# main.net
KiCad netlist of a schematic drawn in EAGLE
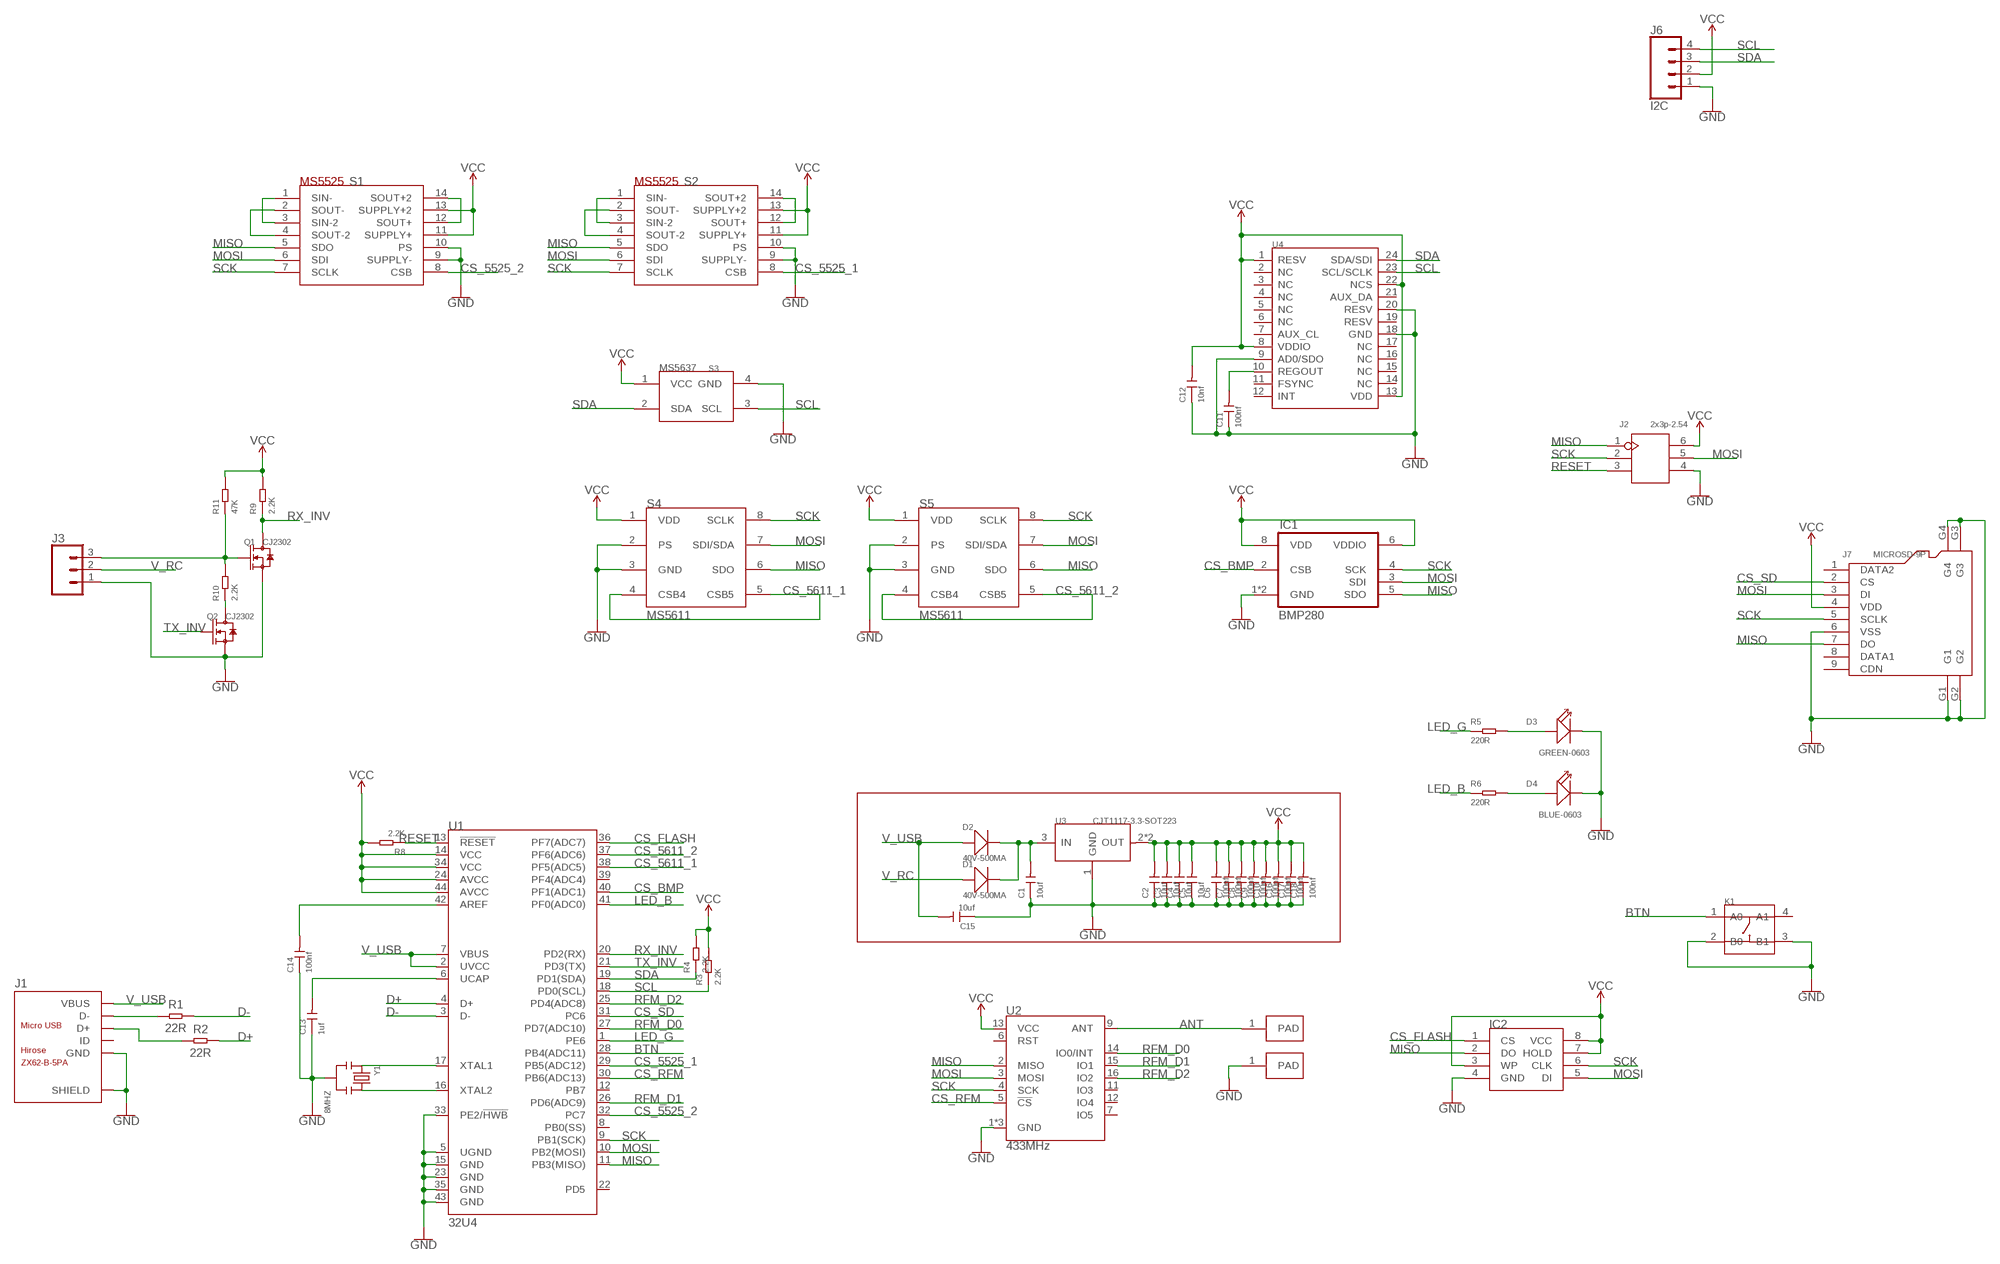
[diagram p0: schematic, sheet 1]

(export (version "E")
  (design (tool "Eeschema 10.0.6"))
  (components
    (comp (ref "C1")
      (value "10uf")
      (footprint "eagle-import:C0805")
      (fields (field (name "MPN") "CC0805KKX5R8BB106"))
      (libsource (lib "eagle-import") (part "CERAMIC-10UF-25V-10%-X5R(0805)"))
    )
    (comp (ref "C2")
      (value "10uf")
      (footprint "eagle-import:C0805")
      (fields (field (name "MPN") "CC0805KKX5R8BB106"))
      (libsource (lib "eagle-import") (part "CERAMIC-10UF-25V-10%-X5R(0805)"))
    )
    (comp (ref "C3")
      (value "10uf")
      (footprint "eagle-import:C0805")
      (fields (field (name "MPN") "CC0805KKX5R8BB106"))
      (libsource (lib "eagle-import") (part "CERAMIC-10UF-25V-10%-X5R(0805)"))
    )
    (comp (ref "C4")
      (value "10uf")
      (footprint "eagle-import:C0805")
      (fields (field (name "MPN") "CC0805KKX5R8BB106"))
      (libsource (lib "eagle-import") (part "CERAMIC-10UF-25V-10%-X5R(0805)"))
    )
    (comp (ref "C5")
      (value "10uf")
      (footprint "eagle-import:C0805")
      (fields (field (name "MPN") "CC0805KKX5R8BB106"))
      (libsource (lib "eagle-import") (part "CERAMIC-10UF-25V-10%-X5R(0805)"))
    )
    (comp (ref "C6")
      (value "100nf")
      (footprint "eagle-import:C0603")
      (fields (field (name "MPN") "CC0603KRX7R9BB104"))
      (libsource (lib "eagle-import") (part "CERAMIC-100NF-50V-10%-X7R(0603)"))
    )
    (comp (ref "C7")
      (value "100nf")
      (footprint "eagle-import:C0603")
      (fields (field (name "MPN") "CC0603KRX7R9BB104"))
      (libsource (lib "eagle-import") (part "CERAMIC-100NF-50V-10%-X7R(0603)"))
    )
    (comp (ref "C8")
      (value "100nf")
      (footprint "eagle-import:C0603")
      (fields (field (name "MPN") "CC0603KRX7R9BB104"))
      (libsource (lib "eagle-import") (part "CERAMIC-100NF-50V-10%-X7R(0603)"))
    )
    (comp (ref "C9")
      (value "100nf")
      (footprint "eagle-import:C0603")
      (fields (field (name "MPN") "CC0603KRX7R9BB104"))
      (libsource (lib "eagle-import") (part "CERAMIC-100NF-50V-10%-X7R(0603)"))
    )
    (comp (ref "C10")
      (value "100nf")
      (footprint "eagle-import:C0603")
      (fields (field (name "MPN") "CC0603KRX7R9BB104"))
      (libsource (lib "eagle-import") (part "CERAMIC-100NF-50V-10%-X7R(0603)"))
    )
    (comp (ref "C11")
      (value "100nf")
      (footprint "eagle-import:C0603")
      (fields (field (name "MPN") "CC0603KRX7R9BB104"))
      (libsource (lib "eagle-import") (part "CERAMIC-100NF-50V-10%-X7R(0603)"))
    )
    (comp (ref "C12")
      (value "10nf")
      (footprint "eagle-import:C0603")
      (fields (field (name "MPN") "CC0603KRX7R9BB103"))
      (libsource (lib "eagle-import") (part "CERAMIC-10NF-50V-10%-X7R(0603)"))
    )
    (comp (ref "C13")
      (value "1uf")
      (footprint "eagle-import:C0603")
      (fields (field (name "MPN") "CC0603KRX7R8BB105"))
      (libsource (lib "eagle-import") (part "CERAMIC-1UF-25V-10%-X7R(0603)"))
    )
    (comp (ref "C14")
      (value "100nf")
      (footprint "eagle-import:C0603")
      (fields (field (name "MPN") "CC0603KRX7R9BB104"))
      (libsource (lib "eagle-import") (part "CERAMIC-100NF-50V-10%-X7R(0603)"))
    )
    (comp (ref "C15")
      (value "10uf")
      (footprint "eagle-import:C0805")
      (fields (field (name "MPN") "CC0805KKX5R8BB106"))
      (libsource (lib "eagle-import") (part "CERAMIC-10UF-25V-10%-X5R(0805)"))
    )
    (comp (ref "C16")
      (value "100nf")
      (footprint "eagle-import:C0603")
      (fields (field (name "MPN") "CC0603KRX7R9BB104"))
      (libsource (lib "eagle-import") (part "CERAMIC-100NF-50V-10%-X7R(0603)"))
    )
    (comp (ref "C17")
      (value "100nf")
      (footprint "eagle-import:C0603")
      (fields (field (name "MPN") "CC0603KRX7R9BB104"))
      (libsource (lib "eagle-import") (part "CERAMIC-100NF-50V-10%-X7R(0603)"))
    )
    (comp (ref "C18")
      (value "100nf")
      (footprint "eagle-import:C0603")
      (fields (field (name "MPN") "CC0603KRX7R9BB104"))
      (libsource (lib "eagle-import") (part "CERAMIC-100NF-50V-10%-X7R(0603)"))
    )
    (comp (ref "D1")
      (value "40V-500MA")
      (footprint "eagle-import:SOD-123")
      (fields (field (name "MPN") "B0540W"))
      (libsource (lib "eagle-import") (part "SMD-DIODE-SCHOTTKY-40V-500MA(SOD-123)"))
    )
    (comp (ref "D2")
      (value "40V-500MA")
      (footprint "eagle-import:SOD-123")
      (fields (field (name "MPN") "B0540W"))
      (libsource (lib "eagle-import") (part "SMD-DIODE-SCHOTTKY-40V-500MA(SOD-123)"))
    )
    (comp (ref "D3")
      (value "GREEN-0603")
      (footprint "eagle-import:LED-0603")
      (fields (field (name "MPN") "19-217-G7C-AN1P2-3T"))
      (libsource (lib "eagle-import") (part "SMD-LED-CLEAR-GREEN(0603)"))
    )
    (comp (ref "D4")
      (value "BLUE-0603")
      (footprint "eagle-import:LED-0603")
      (fields (field (name "MPN") "19-217-BHC-ZL1M2RY-3T"))
      (libsource (lib "eagle-import") (part "SMD-LED-CLEAR-BLUE(0603)"))
    )
    (comp (ref "IC1")
      (value "BMP280")
      (footprint "eagle-import:BMP280")
      (libsource (lib "eagle-import") (part "BMP280"))
    )
    (comp (ref "IC2")
      (value "W25Q32BVWSON8_6X5")
      (footprint "eagle-import:SON127P600X500X75-8")
      (libsource (lib "eagle-import") (part "W25Q32BVWSON8_6X5"))
    )
    (comp (ref "J1")
      (value "ZX62-B-5PA")
      (footprint "eagle-import:MICRO-USB5+6P-SMD-0.65-AB")
      (libsource (lib "eagle-import") (part "MICRO-USB-SMD(ZX62-B-5PA)"))
    )
    (comp (ref "J2")
      (value "2x3p-2.54")
      (footprint "eagle-import:H2X3-2.54")
      (fields (field (name "MPN") "P125-12A1BS116A1"))
      (libsource (lib "eagle-import") (part "DIP-BLACK-MALE-HEADER(2X3P-2.54）-2.54"))
    )
    (comp (ref "J3")
      (value "CONN_03")
      (footprint "eagle-import:1X03")
      (libsource (lib "eagle-import") (part "CONN_03"))
    )
    (comp (ref "J6")
      (value "I2C")
      (footprint "eagle-import:1X04")
      (libsource (lib "eagle-import") (part "CONN_04"))
    )
    (comp (ref "J7")
      (value "MICROSD-9P")
      (footprint "eagle-import:MICRO-SD9+4P-SMD-16.1X14.5X1.85MM")
      (libsource (lib "eagle-import") (part "MICRO-SD-CARD-HOLDER-9P"))
    )
    (comp (ref "K1")
      (value "SMD-SWITCH-TACTILE-SPST-NO(4P-D6.0MM)")
      (footprint "eagle-import:SW4-SMD-6.0X6.0X5.0MM")
      (fields (field (name "MPN") "DTSM-62K-S-V-T/R(SN431)"))
      (libsource (lib "eagle-import") (part "SMD-SWITCH-TACTILE-SPST-NO(4P-D6.0MM)"))
    )
    (comp (ref "Q1")
      (value "CJ2302")
      (footprint "eagle-import:SOT-23")
      (libsource (lib "eagle-import") (part "SMD-MOSFET-N-CH-20V-2.1A-CJ2302(SOT-23)"))
    )
    (comp (ref "Q2")
      (value "CJ2302")
      (footprint "eagle-import:SOT-23")
      (libsource (lib "eagle-import") (part "SMD-MOSFET-N-CH-20V-2.1A-CJ2302(SOT-23)"))
    )
    (comp (ref "R1")
      (value "22R")
      (footprint "eagle-import:R0603")
      (fields (field (name "MPN") "RC0603JR-0722RL"))
      (libsource (lib "eagle-import") (part "SMD-RES-22R-5%-1/10W(0603)"))
    )
    (comp (ref "R2")
      (value "22R")
      (footprint "eagle-import:R0603")
      (fields (field (name "MPN") "RC0603JR-0722RL"))
      (libsource (lib "eagle-import") (part "SMD-RES-22R-5%-1/10W(0603)"))
    )
    (comp (ref "R3")
      (value "2.2K")
      (footprint "eagle-import:R0603")
      (fields (field (name "MPN") "RC0603JR-072K2L"))
      (libsource (lib "eagle-import") (part "SMD-RES-2.2K-5%-1/10W(0603)"))
    )
    (comp (ref "R4")
      (value "2.2K")
      (footprint "eagle-import:R0603")
      (fields (field (name "MPN") "RC0603JR-072K2L"))
      (libsource (lib "eagle-import") (part "SMD-RES-2.2K-5%-1/10W(0603)"))
    )
    (comp (ref "R5")
      (value "220R")
      (footprint "eagle-import:R0603")
      (fields (field (name "MPN") "RC0603JR-07220RL"))
      (libsource (lib "eagle-import") (part "SMD-RES-220R-5%-1/10W(0603)"))
    )
    (comp (ref "R6")
      (value "220R")
      (footprint "eagle-import:R0603")
      (fields (field (name "MPN") "RC0603JR-07220RL"))
      (libsource (lib "eagle-import") (part "SMD-RES-220R-5%-1/10W(0603)"))
    )
    (comp (ref "R8")
      (value "2.2K")
      (footprint "eagle-import:R0603")
      (fields (field (name "MPN") "RC0603JR-072K2L"))
      (libsource (lib "eagle-import") (part "SMD-RES-2.2K-5%-1/10W(0603)"))
    )
    (comp (ref "R9")
      (value "2.2K")
      (footprint "eagle-import:R0603")
      (fields (field (name "MPN") "RC0603JR-072K2L"))
      (libsource (lib "eagle-import") (part "SMD-RES-2.2K-5%-1/10W(0603)"))
    )
    (comp (ref "R10")
      (value "2.2K")
      (footprint "eagle-import:R0603")
      (fields (field (name "MPN") "RC0603JR-072K2L"))
      (libsource (lib "eagle-import") (part "SMD-RES-2.2K-5%-1/10W(0603)"))
    )
    (comp (ref "R11")
      (value "47K")
      (footprint "eagle-import:R0603")
      (fields (field (name "MPN") "RC0603JR-0747KL"))
      (libsource (lib "eagle-import") (part "SMD-RES-47K-5%-1/10W(0603)"))
    )
    (comp (ref "S1")
      (value "MS5525")
      (footprint "eagle-import:SOIC14-WIDE")
      (libsource (lib "eagle-import") (part "MS5525"))
    )
    (comp (ref "S2")
      (value "MS5525")
      (footprint "eagle-import:SOIC14-WIDE")
      (libsource (lib "eagle-import") (part "MS5525"))
    )
    (comp (ref "S3")
      (value "MS5637")
      (footprint "eagle-import:MS5637")
      (libsource (lib "eagle-import") (part "MS5637"))
    )
    (comp (ref "S4")
      (value "MS5611")
      (footprint "eagle-import:MS5611")
      (libsource (lib "eagle-import") (part "MS5611"))
    )
    (comp (ref "S5")
      (value "MS5611")
      (footprint "eagle-import:MS5611")
      (libsource (lib "eagle-import") (part "MS5611"))
    )
    (comp (ref "U$1")
      (value "PADPAD_2.5X1.5")
      (footprint "eagle-import:PAD_2.5X1.5")
      (libsource (lib "eagle-import") (part "PADPAD_2.5X1.5"))
    )
    (comp (ref "U$2")
      (value "PADPAD_2.5X1.5")
      (footprint "eagle-import:PAD_2.5X1.5")
      (libsource (lib "eagle-import") (part "PADPAD_2.5X1.5"))
    )
    (comp (ref "U1")
      (value "32U4")
      (footprint "eagle-import:QFN-44-NOPAD_1_1")
      (libsource (lib "eagle-import") (part "ATMEGA32U41{colon}1"))
    )
    (comp (ref "U2")
      (value "433MHz")
      (footprint "eagle-import:RFM69HCW-XXXS2")
      (libsource (lib "eagle-import") (part "RFM69HCW-433"))
    )
    (comp (ref "U3")
      (value "CJT1117-3.3-SOT223")
      (footprint "eagle-import:SOT-223")
      (fields (field (name "MPN") "CJT1117-3.3"))
      (libsource (lib "eagle-import") (part "PMIC-CJT1117-3.3(SOT223)"))
    )
    (comp (ref "U4")
      (value "MOTION/POSITION-MPU-9250(QFN24G)")
      (footprint "eagle-import:QFN24G-0.4-3X3MM")
      (libsource (lib "eagle-import") (part "MOTION/POSITION-MPU-9250(QFN24G)"))
    )
    (comp (ref "Y1")
      (value "8MHZ")
      (footprint "eagle-import:X3-SMD-3.6X1.3X0.8MM")
      (libsource (lib "eagle-import") (part "SMD-CRYSTAL-8MHZ--0.3%-150R(3P-3.6X1.3MM)"))
    )
  )
  (nets
    (net (code "1") (name "/ANT") (class "Default")
      (node (ref "U$2") (pin "1") (pinfunction "PAD_1") (pintype "bidirectional"))
      (node (ref "U2") (pin "9") (pinfunction "ANT_9") (pintype "passive"))
    )
    (net (code "2") (name "/BTN") (class "Default")
      (node (ref "K1") (pin "1") (pinfunction "A0_1") (pintype "bidirectional"))
      (node (ref "U1") (pin "28") (pinfunction "PB4(ADC11)_28") (pintype "bidirectional"))
    )
    (net (code "3") (name "/CS_5525_1") (class "Default")
      (node (ref "S2") (pin "8") (pinfunction "CSB_8") (pintype "bidirectional"))
      (node (ref "U1") (pin "29") (pinfunction "PB5(ADC12)_29") (pintype "bidirectional"))
    )
    (net (code "4") (name "/CS_5525_2") (class "Default")
      (node (ref "S1") (pin "8") (pinfunction "CSB_8") (pintype "bidirectional"))
      (node (ref "U1") (pin "32") (pinfunction "PC7_32") (pintype "bidirectional"))
    )
    (net (code "5") (name "/CS_5611_1") (class "Default")
      (node (ref "S4") (pin "4") (pinfunction "CSB4_4") (pintype "bidirectional"))
      (node (ref "S4") (pin "5") (pinfunction "CSB5_5") (pintype "bidirectional"))
      (node (ref "U1") (pin "38") (pinfunction "PF5(ADC5)_38") (pintype "bidirectional"))
    )
    (net (code "6") (name "/CS_5611_2") (class "Default")
      (node (ref "S5") (pin "4") (pinfunction "CSB4_4") (pintype "bidirectional"))
      (node (ref "S5") (pin "5") (pinfunction "CSB5_5") (pintype "bidirectional"))
      (node (ref "U1") (pin "37") (pinfunction "PF6(ADC6)_37") (pintype "bidirectional"))
    )
    (net (code "7") (name "/CS_BMP") (class "Default")
      (node (ref "IC1") (pin "2") (pinfunction "CSB_2") (pintype "input"))
      (node (ref "U1") (pin "40") (pinfunction "PF1(ADC1)_40") (pintype "bidirectional"))
    )
    (net (code "8") (name "/CS_FLASH") (class "Default")
      (node (ref "IC2") (pin "1") (pinfunction "CS_1") (pintype "bidirectional"))
      (node (ref "U1") (pin "36") (pinfunction "PF7(ADC7)_36") (pintype "bidirectional"))
    )
    (net (code "9") (name "/CS_RFM") (class "Default")
      (node (ref "U1") (pin "30") (pinfunction "PB6(ADC13)_30") (pintype "bidirectional"))
      (node (ref "U2") (pin "5") (pinfunction "~{CS}_5") (pintype "input"))
    )
    (net (code "10") (name "/CS_SD") (class "Default")
      (node (ref "J7") (pin "2") (pinfunction "CS_2") (pintype "bidirectional"))
      (node (ref "U1") (pin "31") (pinfunction "PC6_31") (pintype "bidirectional"))
    )
    (net (code "11") (name "/D+") (class "Default")
      (node (ref "R2") (pin "2") (pinfunction "2_2") (pintype "passive"))
      (node (ref "U1") (pin "4") (pinfunction "D+_4") (pintype "bidirectional"))
    )
    (net (code "12") (name "/D-") (class "Default")
      (node (ref "R1") (pin "2") (pinfunction "2_2") (pintype "passive"))
      (node (ref "U1") (pin "3") (pinfunction "D-_3") (pintype "bidirectional"))
    )
    (net (code "13") (name "/LED_B") (class "Default")
      (node (ref "R6") (pin "1") (pinfunction "1_1") (pintype "passive"))
      (node (ref "U1") (pin "41") (pinfunction "PF0(ADC0)_41") (pintype "bidirectional"))
    )
    (net (code "14") (name "/LED_G") (class "Default")
      (node (ref "R5") (pin "1") (pinfunction "1_1") (pintype "passive"))
      (node (ref "U1") (pin "1") (pinfunction "PE6_1") (pintype "bidirectional"))
    )
    (net (code "15") (name "/MISO") (class "Default")
      (node (ref "IC1") (pin "5") (pinfunction "SDO_5") (pintype "input"))
      (node (ref "IC2") (pin "2") (pinfunction "DO_2") (pintype "bidirectional"))
      (node (ref "J2") (pin "1") (pinfunction "1_1") (pintype "bidirectional"))
      (node (ref "J7") (pin "7") (pinfunction "DO_7") (pintype "bidirectional"))
      (node (ref "S1") (pin "5") (pinfunction "SDO_5") (pintype "bidirectional"))
      (node (ref "S2") (pin "5") (pinfunction "SDO_5") (pintype "bidirectional"))
      (node (ref "S4") (pin "6") (pinfunction "SDO_6") (pintype "bidirectional"))
      (node (ref "S5") (pin "6") (pinfunction "SDO_6") (pintype "bidirectional"))
      (node (ref "U1") (pin "11") (pinfunction "PB3(MISO)_11") (pintype "bidirectional"))
      (node (ref "U2") (pin "2") (pinfunction "MISO_2") (pintype "bidirectional"))
    )
    (net (code "16") (name "/MOSI") (class "Default")
      (node (ref "IC1") (pin "3") (pinfunction "SDI_3") (pintype "bidirectional"))
      (node (ref "IC2") (pin "5") (pinfunction "DI_5") (pintype "bidirectional"))
      (node (ref "J2") (pin "5") (pinfunction "5_5") (pintype "bidirectional"))
      (node (ref "J7") (pin "3") (pinfunction "DI_3") (pintype "bidirectional"))
      (node (ref "S1") (pin "6") (pinfunction "SDI_6") (pintype "bidirectional"))
      (node (ref "S2") (pin "6") (pinfunction "SDI_6") (pintype "bidirectional"))
      (node (ref "S4") (pin "7") (pinfunction "SDI/SDA_7") (pintype "bidirectional"))
      (node (ref "S5") (pin "7") (pinfunction "SDI/SDA_7") (pintype "bidirectional"))
      (node (ref "U1") (pin "10") (pinfunction "PB2(MOSI)_10") (pintype "bidirectional"))
      (node (ref "U2") (pin "3") (pinfunction "MOSI_3") (pintype "input"))
    )
    (net (code "17") (name "/RESET") (class "Default")
      (node (ref "J2") (pin "3") (pinfunction "3_3") (pintype "bidirectional"))
      (node (ref "R8") (pin "1") (pinfunction "1_1") (pintype "passive"))
      (node (ref "U1") (pin "13") (pinfunction "~{RESET}_13") (pintype "bidirectional"))
    )
    (net (code "18") (name "/RFM_D0") (class "Default")
      (node (ref "U1") (pin "27") (pinfunction "PD7(ADC10)_27") (pintype "bidirectional"))
      (node (ref "U2") (pin "14") (pinfunction "IO0/INT_14") (pintype "bidirectional"))
    )
    (net (code "19") (name "/RFM_D1") (class "Default")
      (node (ref "U1") (pin "26") (pinfunction "PD6(ADC9)_26") (pintype "bidirectional"))
      (node (ref "U2") (pin "15") (pinfunction "IO1_15") (pintype "bidirectional"))
    )
    (net (code "20") (name "/RFM_D2") (class "Default")
      (node (ref "U1") (pin "25") (pinfunction "PD4(ADC8)_25") (pintype "bidirectional"))
      (node (ref "U2") (pin "16") (pinfunction "IO2_16") (pintype "bidirectional"))
    )
    (net (code "21") (name "/RX_INV") (class "Default")
      (node (ref "Q1") (pin "3") (pinfunction "D_3") (pintype "passive"))
      (node (ref "R9") (pin "1") (pinfunction "1_1") (pintype "passive"))
      (node (ref "U1") (pin "20") (pinfunction "PD2(RX)_20") (pintype "bidirectional"))
    )
    (net (code "22") (name "/SCK") (class "Default")
      (node (ref "IC1") (pin "4") (pinfunction "SCK_4") (pintype "bidirectional"))
      (node (ref "IC2") (pin "6") (pinfunction "CLK_6") (pintype "bidirectional"))
      (node (ref "J2") (pin "2") (pinfunction "2_2") (pintype "bidirectional"))
      (node (ref "J7") (pin "5") (pinfunction "SCLK_5") (pintype "bidirectional"))
      (node (ref "S1") (pin "7") (pinfunction "SCLK_7") (pintype "bidirectional"))
      (node (ref "S2") (pin "7") (pinfunction "SCLK_7") (pintype "bidirectional"))
      (node (ref "S4") (pin "8") (pinfunction "SCLK_8") (pintype "bidirectional"))
      (node (ref "S5") (pin "8") (pinfunction "SCLK_8") (pintype "bidirectional"))
      (node (ref "U1") (pin "9") (pinfunction "PB1(SCK)_9") (pintype "bidirectional"))
      (node (ref "U2") (pin "4") (pinfunction "SCK_4") (pintype "input"))
    )
    (net (code "23") (name "/SCL") (class "Default")
      (node (ref "J6") (pin "4") (pinfunction "4_4") (pintype "passive"))
      (node (ref "R3") (pin "1") (pinfunction "1_1") (pintype "passive"))
      (node (ref "S3") (pin "3") (pinfunction "SCL_3") (pintype "bidirectional"))
      (node (ref "U1") (pin "18") (pinfunction "PD0(SCL)_18") (pintype "bidirectional"))
      (node (ref "U4") (pin "23") (pinfunction "SCL/SCLK_23") (pintype "bidirectional"))
    )
    (net (code "24") (name "/SDA") (class "Default")
      (node (ref "J6") (pin "3") (pinfunction "3_3") (pintype "passive"))
      (node (ref "R4") (pin "1") (pinfunction "1_1") (pintype "passive"))
      (node (ref "S3") (pin "2") (pinfunction "SDA_2") (pintype "bidirectional"))
      (node (ref "U1") (pin "19") (pinfunction "PD1(SDA)_19") (pintype "bidirectional"))
      (node (ref "U4") (pin "24") (pinfunction "SDA/SDI_24") (pintype "bidirectional"))
    )
    (net (code "25") (name "/TX_INV") (class "Default")
      (node (ref "Q2") (pin "1") (pinfunction "G_1") (pintype "passive"))
      (node (ref "U1") (pin "21") (pinfunction "PD3(TX)_21") (pintype "bidirectional"))
    )
    (net (code "26") (name "/V_RC") (class "Default")
      (node (ref "D1") (pin "+") (pinfunction "+_+") (pintype "passive"))
      (node (ref "J3") (pin "2") (pinfunction "2_2") (pintype "passive"))
    )
    (net (code "27") (name "/V_USB") (class "Default")
      (node (ref "C15") (pin "2") (pinfunction "2_2") (pintype "passive"))
      (node (ref "D2") (pin "+") (pinfunction "+_+") (pintype "passive"))
      (node (ref "J1") (pin "1") (pinfunction "VBUS_1") (pintype "power_in"))
      (node (ref "U1") (pin "2") (pinfunction "UVCC_2") (pintype "bidirectional"))
      (node (ref "U1") (pin "7") (pinfunction "VBUS_7") (pintype "bidirectional"))
    )
    (net (code "28") (name "GND") (class "Default")
      (node (ref "C1") (pin "1") (pinfunction "1_1") (pintype "passive"))
      (node (ref "C10") (pin "1") (pinfunction "1_1") (pintype "passive"))
      (node (ref "C11") (pin "1") (pinfunction "1_1") (pintype "passive"))
      (node (ref "C12") (pin "1") (pinfunction "1_1") (pintype "passive"))
      (node (ref "C13") (pin "1") (pinfunction "1_1") (pintype "passive"))
      (node (ref "C14") (pin "1") (pinfunction "1_1") (pintype "passive"))
      (node (ref "C15") (pin "1") (pinfunction "1_1") (pintype "passive"))
      (node (ref "C16") (pin "1") (pinfunction "1_1") (pintype "passive"))
      (node (ref "C17") (pin "1") (pinfunction "1_1") (pintype "passive"))
      (node (ref "C18") (pin "1") (pinfunction "1_1") (pintype "passive"))
      (node (ref "C2") (pin "1") (pinfunction "1_1") (pintype "passive"))
      (node (ref "C3") (pin "1") (pinfunction "1_1") (pintype "passive"))
      (node (ref "C4") (pin "1") (pinfunction "1_1") (pintype "passive"))
      (node (ref "C5") (pin "1") (pinfunction "1_1") (pintype "passive"))
      (node (ref "C6") (pin "1") (pinfunction "1_1") (pintype "passive"))
      (node (ref "C7") (pin "1") (pinfunction "1_1") (pintype "passive"))
      (node (ref "C8") (pin "1") (pinfunction "1_1") (pintype "passive"))
      (node (ref "C9") (pin "1") (pinfunction "1_1") (pintype "passive"))
      (node (ref "D3") (pin "-") (pinfunction "-_-") (pintype "passive"))
      (node (ref "D4") (pin "-") (pinfunction "-_-") (pintype "passive"))
      (node (ref "IC1") (pin "1") (pinfunction "GND_1") (pintype "power_in"))
      (node (ref "IC1") (pin "7") (pinfunction "GND_7") (pintype "power_in"))
      (node (ref "IC2") (pin "4") (pinfunction "GND_4") (pintype "bidirectional"))
      (node (ref "J1") (pin "5") (pinfunction "GND_5") (pintype "power_in"))
      (node (ref "J1") (pin "P1") (pinfunction "SHIELD_P1") (pintype "power_in"))
      (node (ref "J1") (pin "P2") (pinfunction "SHIELD_P2") (pintype "power_in"))
      (node (ref "J1") (pin "P3") (pinfunction "SHIELD_P3") (pintype "power_in"))
      (node (ref "J1") (pin "P4") (pinfunction "SHIELD_P4") (pintype "power_in"))
      (node (ref "J1") (pin "P5") (pinfunction "SHIELD_P5") (pintype "power_in"))
      (node (ref "J1") (pin "P6") (pinfunction "SHIELD_P6") (pintype "power_in"))
      (node (ref "J2") (pin "4") (pinfunction "4_4") (pintype "bidirectional"))
      (node (ref "J3") (pin "1") (pinfunction "1_1") (pintype "passive"))
      (node (ref "J6") (pin "1") (pinfunction "1_1") (pintype "passive"))
      (node (ref "J7") (pin "6") (pinfunction "VSS_6") (pintype "bidirectional"))
      (node (ref "J7") (pin "G1") (pinfunction "G1_G1") (pintype "bidirectional"))
      (node (ref "J7") (pin "G2") (pinfunction "G2_G2") (pintype "bidirectional"))
      (node (ref "J7") (pin "G3") (pinfunction "G3_G3") (pintype "bidirectional"))
      (node (ref "J7") (pin "G4") (pinfunction "G4_G4") (pintype "bidirectional"))
      (node (ref "K1") (pin "2") (pinfunction "B0_2") (pintype "bidirectional"))
      (node (ref "K1") (pin "3") (pinfunction "B1_3") (pintype "bidirectional"))
      (node (ref "Q1") (pin "2") (pinfunction "S_2") (pintype "passive"))
      (node (ref "Q2") (pin "2") (pinfunction "S_2") (pintype "passive"))
      (node (ref "S1") (pin "10") (pinfunction "PS_10") (pintype "bidirectional"))
      (node (ref "S1") (pin "9") (pinfunction "SUPPLY-_9") (pintype "bidirectional"))
      (node (ref "S2") (pin "10") (pinfunction "PS_10") (pintype "bidirectional"))
      (node (ref "S2") (pin "9") (pinfunction "SUPPLY-_9") (pintype "bidirectional"))
      (node (ref "S3") (pin "4") (pinfunction "GND_4") (pintype "bidirectional"))
      (node (ref "S4") (pin "2") (pinfunction "PS_2") (pintype "bidirectional"))
      (node (ref "S4") (pin "3") (pinfunction "GND_3") (pintype "bidirectional"))
      (node (ref "S5") (pin "2") (pinfunction "PS_2") (pintype "bidirectional"))
      (node (ref "S5") (pin "3") (pinfunction "GND_3") (pintype "bidirectional"))
      (node (ref "U$1") (pin "1") (pinfunction "PAD_1") (pintype "bidirectional"))
      (node (ref "U1") (pin "15") (pinfunction "GND_15") (pintype "bidirectional"))
      (node (ref "U1") (pin "23") (pinfunction "GND_23") (pintype "bidirectional"))
      (node (ref "U1") (pin "33") (pinfunction "PE2/~{HWB}_33") (pintype "bidirectional"))
      (node (ref "U1") (pin "35") (pinfunction "GND_35") (pintype "bidirectional"))
      (node (ref "U1") (pin "43") (pinfunction "GND_43") (pintype "bidirectional"))
      (node (ref "U1") (pin "5") (pinfunction "UGND_5") (pintype "bidirectional"))
      (node (ref "U2") (pin "1") (pinfunction "GND_1") (pintype "power_in"))
      (node (ref "U2") (pin "10") (pinfunction "GND_10") (pintype "power_in"))
      (node (ref "U2") (pin "8") (pinfunction "GND_8") (pintype "power_in"))
      (node (ref "U3") (pin "1") (pinfunction "GND_1") (pintype "bidirectional"))
      (node (ref "U4") (pin "18") (pinfunction "GND_18") (pintype "bidirectional"))
      (node (ref "U4") (pin "20") (pinfunction "RESV_20") (pintype "bidirectional"))
      (node (ref "U4") (pin "9") (pinfunction "AD0/SDO_9") (pintype "bidirectional"))
      (node (ref "Y1") (pin "2") (pinfunction "2_2") (pintype "passive"))
    )
    (net (code "29") (name "Net-(D3-Pad+)") (class "Default")
      (node (ref "D3") (pin "+") (pinfunction "+_+") (pintype "passive"))
      (node (ref "R5") (pin "2") (pinfunction "2_2") (pintype "passive"))
    )
    (net (code "30") (name "Net-(D4-Pad+)") (class "Default")
      (node (ref "D4") (pin "+") (pinfunction "+_+") (pintype "passive"))
      (node (ref "R6") (pin "2") (pinfunction "2_2") (pintype "passive"))
    )
    (net (code "31") (name "Net-(J1-D+)") (class "Default")
      (node (ref "J1") (pin "3") (pinfunction "D+_3") (pintype "bidirectional"))
      (node (ref "R2") (pin "1") (pinfunction "1_1") (pintype "passive"))
    )
    (net (code "32") (name "Net-(J1-D-)") (class "Default")
      (node (ref "J1") (pin "2") (pinfunction "D-_2") (pintype "bidirectional"))
      (node (ref "R1") (pin "1") (pinfunction "1_1") (pintype "passive"))
    )
    (net (code "33") (name "Net-(Q1-G)") (class "Default")
      (node (ref "J3") (pin "3") (pinfunction "3_3") (pintype "passive"))
      (node (ref "Q1") (pin "1") (pinfunction "G_1") (pintype "passive"))
      (node (ref "R10") (pin "2") (pinfunction "2_2") (pintype "passive"))
      (node (ref "R11") (pin "1") (pinfunction "1_1") (pintype "passive"))
    )
    (net (code "34") (name "Net-(Q2-D)") (class "Default")
      (node (ref "Q2") (pin "3") (pinfunction "D_3") (pintype "passive"))
      (node (ref "R10") (pin "1") (pinfunction "1_1") (pintype "passive"))
    )
    (net (code "35") (name "Net-(S1-SIN-)") (class "Default")
      (node (ref "S1") (pin "1") (pinfunction "SIN-_1") (pintype "bidirectional"))
      (node (ref "S1") (pin "3") (pinfunction "SIN-2_3") (pintype "bidirectional"))
    )
    (net (code "36") (name "Net-(S1-SOUT+)") (class "Default")
      (node (ref "S1") (pin "12") (pinfunction "SOUT+_12") (pintype "bidirectional"))
      (node (ref "S1") (pin "14") (pinfunction "SOUT+2_14") (pintype "bidirectional"))
    )
    (net (code "37") (name "Net-(S1-SOUT-)") (class "Default")
      (node (ref "S1") (pin "2") (pinfunction "SOUT-_2") (pintype "bidirectional"))
      (node (ref "S1") (pin "4") (pinfunction "SOUT-2_4") (pintype "bidirectional"))
    )
    (net (code "38") (name "Net-(S2-SIN-)") (class "Default")
      (node (ref "S2") (pin "1") (pinfunction "SIN-_1") (pintype "bidirectional"))
      (node (ref "S2") (pin "3") (pinfunction "SIN-2_3") (pintype "bidirectional"))
    )
    (net (code "39") (name "Net-(S2-SOUT+)") (class "Default")
      (node (ref "S2") (pin "12") (pinfunction "SOUT+_12") (pintype "bidirectional"))
      (node (ref "S2") (pin "14") (pinfunction "SOUT+2_14") (pintype "bidirectional"))
    )
    (net (code "40") (name "Net-(S2-SOUT-)") (class "Default")
      (node (ref "S2") (pin "2") (pinfunction "SOUT-_2") (pintype "bidirectional"))
      (node (ref "S2") (pin "4") (pinfunction "SOUT-2_4") (pintype "bidirectional"))
    )
    (net (code "41") (name "Net-(U1-AREF)") (class "Default")
      (node (ref "C14") (pin "2") (pinfunction "2_2") (pintype "passive"))
      (node (ref "U1") (pin "42") (pinfunction "AREF_42") (pintype "bidirectional"))
    )
    (net (code "42") (name "Net-(U1-UCAP)") (class "Default")
      (node (ref "C13") (pin "2") (pinfunction "2_2") (pintype "passive"))
      (node (ref "U1") (pin "6") (pinfunction "UCAP_6") (pintype "bidirectional"))
    )
    (net (code "43") (name "Net-(U1-XTAL1)") (class "Default")
      (node (ref "U1") (pin "17") (pinfunction "XTAL1_17") (pintype "bidirectional"))
      (node (ref "Y1") (pin "1") (pinfunction "1_1") (pintype "passive"))
    )
    (net (code "44") (name "Net-(U1-XTAL2)") (class "Default")
      (node (ref "U1") (pin "16") (pinfunction "XTAL2_16") (pintype "bidirectional"))
      (node (ref "Y1") (pin "3") (pinfunction "3_3") (pintype "passive"))
    )
    (net (code "45") (name "Net-(U3-IN)") (class "Default")
      (node (ref "C1") (pin "2") (pinfunction "2_2") (pintype "passive"))
      (node (ref "D1") (pin "-") (pinfunction "-_-") (pintype "passive"))
      (node (ref "D2") (pin "-") (pinfunction "-_-") (pintype "passive"))
      (node (ref "U3") (pin "3") (pinfunction "IN_3") (pintype "bidirectional"))
    )
    (net (code "46") (name "Net-(U4-REGOUT)") (class "Default")
      (node (ref "C11") (pin "2") (pinfunction "2_2") (pintype "passive"))
      (node (ref "U4") (pin "10") (pinfunction "REGOUT_10") (pintype "bidirectional"))
    )
    (net (code "47") (name "VCC") (class "Default")
      (node (ref "C10") (pin "2") (pinfunction "2_2") (pintype "passive"))
      (node (ref "C12") (pin "2") (pinfunction "2_2") (pintype "passive"))
      (node (ref "C16") (pin "2") (pinfunction "2_2") (pintype "passive"))
      (node (ref "C17") (pin "2") (pinfunction "2_2") (pintype "passive"))
      (node (ref "C18") (pin "2") (pinfunction "2_2") (pintype "passive"))
      (node (ref "C2") (pin "2") (pinfunction "2_2") (pintype "passive"))
      (node (ref "C3") (pin "2") (pinfunction "2_2") (pintype "passive"))
      (node (ref "C4") (pin "2") (pinfunction "2_2") (pintype "passive"))
      (node (ref "C5") (pin "2") (pinfunction "2_2") (pintype "passive"))
      (node (ref "C6") (pin "2") (pinfunction "2_2") (pintype "passive"))
      (node (ref "C7") (pin "2") (pinfunction "2_2") (pintype "passive"))
      (node (ref "C8") (pin "2") (pinfunction "2_2") (pintype "passive"))
      (node (ref "C9") (pin "2") (pinfunction "2_2") (pintype "passive"))
      (node (ref "IC1") (pin "6") (pinfunction "VDDIO_6") (pintype "power_in"))
      (node (ref "IC1") (pin "8") (pinfunction "VDD_8") (pintype "power_in"))
      (node (ref "IC2") (pin "3") (pinfunction "WP_3") (pintype "bidirectional"))
      (node (ref "IC2") (pin "7") (pinfunction "HOLD_7") (pintype "bidirectional"))
      (node (ref "IC2") (pin "8") (pinfunction "VCC_8") (pintype "bidirectional"))
      (node (ref "J2") (pin "6") (pinfunction "6_6") (pintype "bidirectional"))
      (node (ref "J6") (pin "2") (pinfunction "2_2") (pintype "passive"))
      (node (ref "J7") (pin "4") (pinfunction "VDD_4") (pintype "bidirectional"))
      (node (ref "R11") (pin "2") (pinfunction "2_2") (pintype "passive"))
      (node (ref "R3") (pin "2") (pinfunction "2_2") (pintype "passive"))
      (node (ref "R4") (pin "2") (pinfunction "2_2") (pintype "passive"))
      (node (ref "R8") (pin "2") (pinfunction "2_2") (pintype "passive"))
      (node (ref "R9") (pin "2") (pinfunction "2_2") (pintype "passive"))
      (node (ref "S1") (pin "11") (pinfunction "SUPPLY+_11") (pintype "bidirectional"))
      (node (ref "S1") (pin "13") (pinfunction "SUPPLY+2_13") (pintype "bidirectional"))
      (node (ref "S2") (pin "11") (pinfunction "SUPPLY+_11") (pintype "bidirectional"))
      (node (ref "S2") (pin "13") (pinfunction "SUPPLY+2_13") (pintype "bidirectional"))
      (node (ref "S3") (pin "1") (pinfunction "VCC_1") (pintype "bidirectional"))
      (node (ref "S4") (pin "1") (pinfunction "VDD_1") (pintype "bidirectional"))
      (node (ref "S5") (pin "1") (pinfunction "VDD_1") (pintype "bidirectional"))
      (node (ref "U1") (pin "14") (pinfunction "VCC_14") (pintype "bidirectional"))
      (node (ref "U1") (pin "24") (pinfunction "AVCC_24") (pintype "bidirectional"))
      (node (ref "U1") (pin "34") (pinfunction "VCC_34") (pintype "bidirectional"))
      (node (ref "U1") (pin "44") (pinfunction "AVCC_44") (pintype "bidirectional"))
      (node (ref "U2") (pin "13") (pinfunction "VCC_13") (pintype "power_in"))
      (node (ref "U3") (pin "2") (pinfunction "OUT_2") (pintype "bidirectional"))
      (node (ref "U3") (pin "TER") (pinfunction "OUT_TER") (pintype "bidirectional"))
      (node (ref "U4") (pin "1") (pinfunction "RESV_1") (pintype "bidirectional"))
      (node (ref "U4") (pin "13") (pinfunction "VDD_13") (pintype "bidirectional"))
      (node (ref "U4") (pin "22") (pinfunction "NCS_22") (pintype "bidirectional"))
      (node (ref "U4") (pin "8") (pinfunction "VDDIO_8") (pintype "bidirectional"))
    )
    (net (code "48") (name "unconnected-(J1-ID-Pad4)") (class "Default")
      (node (ref "J1") (pin "4") (pinfunction "ID_4") (pintype "bidirectional"))
    )
    (net (code "49") (name "unconnected-(J7-CDN-Pad9)") (class "Default")
      (node (ref "J7") (pin "9") (pinfunction "CDN_9") (pintype "bidirectional"))
    )
    (net (code "50") (name "unconnected-(J7-DATA1-Pad8)") (class "Default")
      (node (ref "J7") (pin "8") (pinfunction "DATA1_8") (pintype "bidirectional"))
    )
    (net (code "51") (name "unconnected-(J7-DATA2-Pad1)") (class "Default")
      (node (ref "J7") (pin "1") (pinfunction "DATA2_1") (pintype "bidirectional"))
    )
    (net (code "52") (name "unconnected-(K1-A1-Pad4)") (class "Default")
      (node (ref "K1") (pin "4") (pinfunction "A1_4") (pintype "bidirectional"))
    )
    (net (code "53") (name "unconnected-(U1-PB0(SS)-Pad8)") (class "Default")
      (node (ref "U1") (pin "8") (pinfunction "PB0(SS)_8") (pintype "bidirectional"))
    )
    (net (code "54") (name "unconnected-(U1-PB7-Pad12)") (class "Default")
      (node (ref "U1") (pin "12") (pinfunction "PB7_12") (pintype "bidirectional"))
    )
    (net (code "55") (name "unconnected-(U1-PD5-Pad22)") (class "Default")
      (node (ref "U1") (pin "22") (pinfunction "PD5_22") (pintype "bidirectional"))
    )
    (net (code "56") (name "unconnected-(U1-PF4(ADC4)-Pad39)") (class "Default")
      (node (ref "U1") (pin "39") (pinfunction "PF4(ADC4)_39") (pintype "bidirectional"))
    )
    (net (code "57") (name "unconnected-(U2-IO3-Pad11)") (class "Default")
      (node (ref "U2") (pin "11") (pinfunction "IO3_11") (pintype "bidirectional"))
    )
    (net (code "58") (name "unconnected-(U2-IO4-Pad12)") (class "Default")
      (node (ref "U2") (pin "12") (pinfunction "IO4_12") (pintype "bidirectional"))
    )
    (net (code "59") (name "unconnected-(U2-IO5-Pad7)") (class "Default")
      (node (ref "U2") (pin "7") (pinfunction "IO5_7") (pintype "bidirectional"))
    )
    (net (code "60") (name "unconnected-(U2-RST-Pad6)") (class "Default")
      (node (ref "U2") (pin "6") (pinfunction "RST_6") (pintype "input"))
    )
    (net (code "61") (name "unconnected-(U4-AUX_CL-Pad7)") (class "Default")
      (node (ref "U4") (pin "7") (pinfunction "AUX_CL_7") (pintype "bidirectional"))
    )
    (net (code "62") (name "unconnected-(U4-AUX_DA-Pad21)") (class "Default")
      (node (ref "U4") (pin "21") (pinfunction "AUX_DA_21") (pintype "bidirectional"))
    )
    (net (code "63") (name "unconnected-(U4-FSYNC-Pad11)") (class "Default")
      (node (ref "U4") (pin "11") (pinfunction "FSYNC_11") (pintype "bidirectional"))
    )
    (net (code "64") (name "unconnected-(U4-INT-Pad12)") (class "Default")
      (node (ref "U4") (pin "12") (pinfunction "INT_12") (pintype "bidirectional"))
    )
    (net (code "65") (name "unconnected-(U4-NC-Pad2)") (class "Default")
      (node (ref "U4") (pin "2") (pinfunction "NC_2") (pintype "bidirectional"))
    )
    (net (code "66") (name "unconnected-(U4-NC-Pad3)") (class "Default")
      (node (ref "U4") (pin "3") (pinfunction "NC_3") (pintype "bidirectional"))
    )
    (net (code "67") (name "unconnected-(U4-NC-Pad4)") (class "Default")
      (node (ref "U4") (pin "4") (pinfunction "NC_4") (pintype "bidirectional"))
    )
    (net (code "68") (name "unconnected-(U4-NC-Pad5)") (class "Default")
      (node (ref "U4") (pin "5") (pinfunction "NC_5") (pintype "bidirectional"))
    )
    (net (code "69") (name "unconnected-(U4-NC-Pad6)") (class "Default")
      (node (ref "U4") (pin "6") (pinfunction "NC_6") (pintype "bidirectional"))
    )
    (net (code "70") (name "unconnected-(U4-NC-Pad14)") (class "Default")
      (node (ref "U4") (pin "14") (pinfunction "NC_14") (pintype "bidirectional"))
    )
    (net (code "71") (name "unconnected-(U4-NC-Pad15)") (class "Default")
      (node (ref "U4") (pin "15") (pinfunction "NC_15") (pintype "bidirectional"))
    )
    (net (code "72") (name "unconnected-(U4-NC-Pad16)") (class "Default")
      (node (ref "U4") (pin "16") (pinfunction "NC_16") (pintype "bidirectional"))
    )
    (net (code "73") (name "unconnected-(U4-NC-Pad17)") (class "Default")
      (node (ref "U4") (pin "17") (pinfunction "NC_17") (pintype "bidirectional"))
    )
    (net (code "74") (name "unconnected-(U4-RESV-Pad19)") (class "Default")
      (node (ref "U4") (pin "19") (pinfunction "RESV_19") (pintype "bidirectional"))
    )
  )
)
